# 2V5_DRS4_SUPPLY.net
KiCad netlist of a schematic drawn in Altium Designer
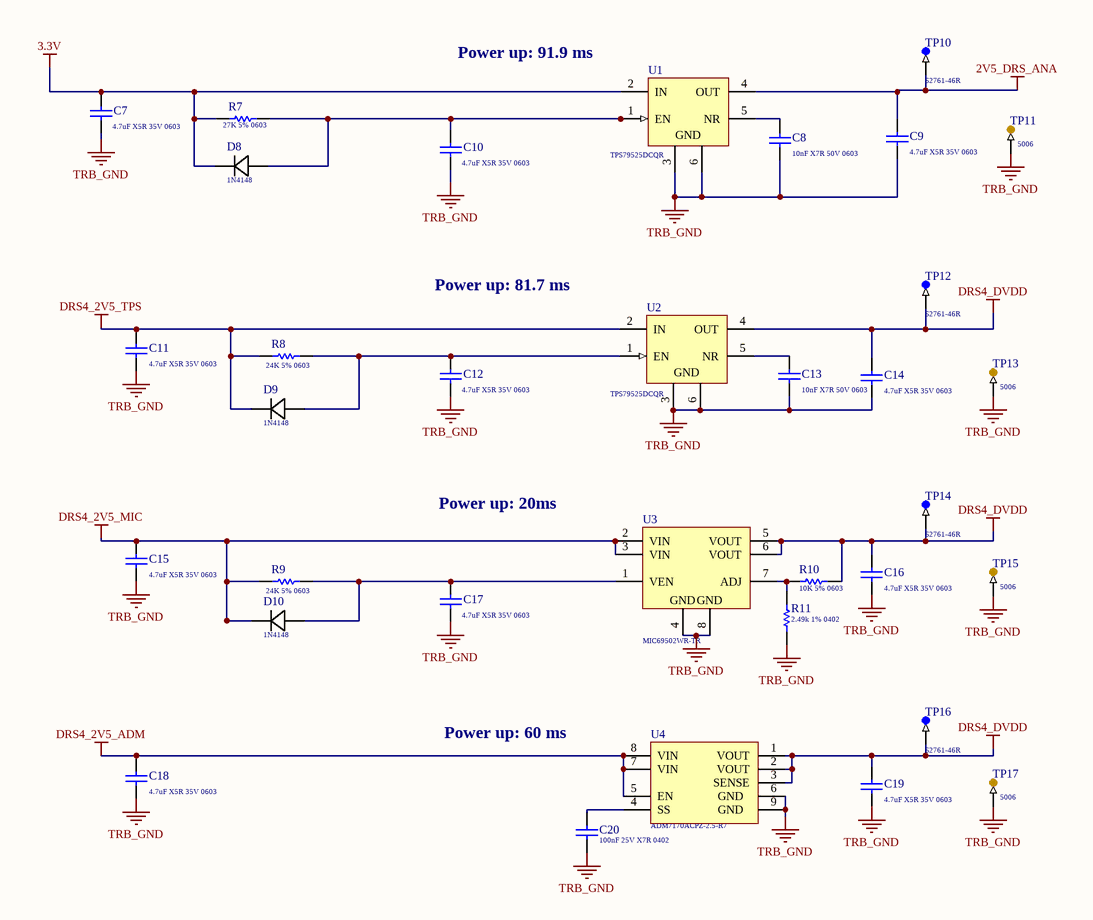
[diagram p0: 2V5_DRS4_SUPPLY.SchDoc]

(export (version "E")
  (design (tool "Eeschema 10.0.6"))
  (components
    (comp (ref "C7")
      (value "Cap_Murata_ZRB18AR6YA475ME05L_4.7uF")
      (footprint "Cap_Murata_ZRB18AR6YA475ME05L_4.7uF")
      (description "CAP CER 4.7uF 35V X5R 0603")
      (fields (field (name "CAPACITANCE") "4.7uF X5R 35V 0603"))
      (libsource (lib "Cap_Murata_ZRB18AR6YA475ME05L_4.7uF") (part "Cap_Murata_ZRB18AR6YA475ME05L_4.7uF"))
    )
    (comp (ref "C8")
      (value "Cap_Kemet_C0603C103J5RACTU_eec")
      (footprint "Kemet_C0603_0")
      (description "CAP CER 10nF 50V X7R 0603")
      (fields
        (field (name "PART NUMBER") "C0603C103J5RACTU")
        (field (name "MANUFACTURER") "Kemet")
        (field (name "CAPACITANCE") "10nF X7R 50V 0603")
      )
      (libsource (lib "Cap_Kemet_C0603C103J5RACTU_10nF") (part "Cap_Kemet_C0603C103J5RACTU_eec"))
    )
    (comp (ref "C9")
      (value "Cap_Murata_ZRB18AR6YA475ME05L_4.7uF")
      (footprint "Cap_Murata_ZRB18AR6YA475ME05L_4.7uF")
      (description "CAP CER 4.7uF 35V X5R 0603")
      (fields (field (name "CAPACITANCE") "4.7uF X5R 35V 0603"))
      (libsource (lib "Cap_Murata_ZRB18AR6YA475ME05L_4.7uF") (part "Cap_Murata_ZRB18AR6YA475ME05L_4.7uF"))
    )
    (comp (ref "C10")
      (value "Cap_Murata_ZRB18AR6YA475ME05L_4.7uF")
      (footprint "Cap_Murata_ZRB18AR6YA475ME05L_4.7uF")
      (description "CAP CER 4.7uF 35V X5R 0603")
      (fields (field (name "CAPACITANCE") "4.7uF X5R 35V 0603"))
      (libsource (lib "Cap_Murata_ZRB18AR6YA475ME05L_4.7uF") (part "Cap_Murata_ZRB18AR6YA475ME05L_4.7uF"))
    )
    (comp (ref "C11")
      (value "Cap_Murata_ZRB18AR6YA475ME05L_4.7uF")
      (footprint "Cap_Murata_ZRB18AR6YA475ME05L_4.7uF")
      (description "CAP CER 4.7uF 35V X5R 0603")
      (fields (field (name "CAPACITANCE") "4.7uF X5R 35V 0603"))
      (libsource (lib "Cap_Murata_ZRB18AR6YA475ME05L_4.7uF") (part "Cap_Murata_ZRB18AR6YA475ME05L_4.7uF"))
    )
    (comp (ref "C12")
      (value "Cap_Murata_ZRB18AR6YA475ME05L_4.7uF")
      (footprint "Cap_Murata_ZRB18AR6YA475ME05L_4.7uF")
      (description "CAP CER 4.7uF 35V X5R 0603")
      (fields (field (name "CAPACITANCE") "4.7uF X5R 35V 0603"))
      (libsource (lib "Cap_Murata_ZRB18AR6YA475ME05L_4.7uF") (part "Cap_Murata_ZRB18AR6YA475ME05L_4.7uF"))
    )
    (comp (ref "C13")
      (value "Cap_Kemet_C0603C103J5RACTU_eec")
      (footprint "Kemet_C0603_0")
      (description "CAP CER 10nF 50V X7R 0603")
      (fields
        (field (name "PART NUMBER") "C0603C103J5RACTU")
        (field (name "MANUFACTURER") "Kemet")
        (field (name "CAPACITANCE") "10nF X7R 50V 0603")
      )
      (libsource (lib "Cap_Kemet_C0603C103J5RACTU_10nF") (part "Cap_Kemet_C0603C103J5RACTU_eec"))
    )
    (comp (ref "C14")
      (value "Cap_Murata_ZRB18AR6YA475ME05L_4.7uF")
      (footprint "Cap_Murata_ZRB18AR6YA475ME05L_4.7uF")
      (description "CAP CER 4.7uF 35V X5R 0603")
      (fields (field (name "CAPACITANCE") "4.7uF X5R 35V 0603"))
      (libsource (lib "Cap_Murata_ZRB18AR6YA475ME05L_4.7uF") (part "Cap_Murata_ZRB18AR6YA475ME05L_4.7uF"))
    )
    (comp (ref "C15")
      (value "Cap_Murata_ZRB18AR6YA475ME05L_4.7uF")
      (footprint "Cap_Murata_ZRB18AR6YA475ME05L_4.7uF")
      (description "CAP CER 4.7uF 35V X5R 0603")
      (fields (field (name "CAPACITANCE") "4.7uF X5R 35V 0603"))
      (libsource (lib "Cap_Murata_ZRB18AR6YA475ME05L_4.7uF") (part "Cap_Murata_ZRB18AR6YA475ME05L_4.7uF"))
    )
    (comp (ref "C16")
      (value "Cap_Murata_ZRB18AR6YA475ME05L_4.7uF")
      (footprint "Cap_Murata_ZRB18AR6YA475ME05L_4.7uF")
      (description "CAP CER 4.7uF 35V X5R 0603")
      (fields (field (name "CAPACITANCE") "4.7uF X5R 35V 0603"))
      (libsource (lib "Cap_Murata_ZRB18AR6YA475ME05L_4.7uF") (part "Cap_Murata_ZRB18AR6YA475ME05L_4.7uF"))
    )
    (comp (ref "C17")
      (value "Cap_Murata_ZRB18AR6YA475ME05L_4.7uF")
      (footprint "Cap_Murata_ZRB18AR6YA475ME05L_4.7uF")
      (description "CAP CER 4.7uF 35V X5R 0603")
      (fields (field (name "CAPACITANCE") "4.7uF X5R 35V 0603"))
      (libsource (lib "Cap_Murata_ZRB18AR6YA475ME05L_4.7uF") (part "Cap_Murata_ZRB18AR6YA475ME05L_4.7uF"))
    )
    (comp (ref "C18")
      (value "Cap_Murata_ZRB18AR6YA475ME05L_4.7uF")
      (footprint "Cap_Murata_ZRB18AR6YA475ME05L_4.7uF")
      (description "CAP CER 4.7uF 35V X5R 0603")
      (fields (field (name "CAPACITANCE") "4.7uF X5R 35V 0603"))
      (libsource (lib "Cap_Murata_ZRB18AR6YA475ME05L_4.7uF") (part "Cap_Murata_ZRB18AR6YA475ME05L_4.7uF"))
    )
    (comp (ref "C19")
      (value "Cap_Murata_ZRB18AR6YA475ME05L_4.7uF")
      (footprint "Cap_Murata_ZRB18AR6YA475ME05L_4.7uF")
      (description "CAP CER 4.7uF 35V X5R 0603")
      (fields (field (name "CAPACITANCE") "4.7uF X5R 35V 0603"))
      (libsource (lib "Cap_Murata_ZRB18AR6YA475ME05L_4.7uF") (part "Cap_Murata_ZRB18AR6YA475ME05L_4.7uF"))
    )
    (comp (ref "C20")
      (value "Cap_Taiyo_Yuden_TMK105B7104KV-FR_100nF")
      (footprint "Cap_Taiyo_Yuden_TMK105B7104KV-FR_100nF")
      (description "CAP CER 100nF 25V X7R 0402")
      (fields (field (name "CAPACITANCE") "100nF 25V X7R 0402"))
      (libsource (lib "Cap_Taiyo_Yuden_TMK105B7104KV-FR_100nF") (part "Cap_Taiyo_Yuden_TMK105B7104KV-FR_100nF"))
    )
    (comp (ref "D8")
      (value "Diode_ON_Semiconductor_1N4148WT_300mA")
      (footprint "Diode_ON_Semiconductor_1N4148WT_300mA")
      (description "Diodes - General Purpose, Power, Switching SINGLE JUNC. 75V 4.0NS COMP")
      (fields (field (name "SERIES") "1N4148"))
      (libsource (lib "Diode_ON_Semiconductor_1N4148WT_300mA") (part "Diode_ON_Semiconductor_1N4148WT_300mA"))
    )
    (comp (ref "D9")
      (value "Diode_ON_Semiconductor_1N4148WT_300mA")
      (footprint "Diode_ON_Semiconductor_1N4148WT_300mA")
      (description "Diodes - General Purpose, Power, Switching SINGLE JUNC. 75V 4.0NS COMP")
      (fields (field (name "SERIES") "1N4148"))
      (libsource (lib "Diode_ON_Semiconductor_1N4148WT_300mA") (part "Diode_ON_Semiconductor_1N4148WT_300mA"))
    )
    (comp (ref "D10")
      (value "Diode_ON_Semiconductor_1N4148WT_300mA")
      (footprint "Diode_ON_Semiconductor_1N4148WT_300mA")
      (description "Diodes - General Purpose, Power, Switching SINGLE JUNC. 75V 4.0NS COMP")
      (fields (field (name "SERIES") "1N4148"))
      (libsource (lib "Diode_ON_Semiconductor_1N4148WT_300mA") (part "Diode_ON_Semiconductor_1N4148WT_300mA"))
    )
    (comp (ref "R7")
      (value "27K 5% 0603")
      (footprint "RESC0603(1608)_L")
      (description "27K 0.1W 5% 0603 (1608 Metric)  SMD")
      (fields (field (name "POWER") "0.1 W") (field (name "TOLERANCE") "5 %"))
      (libsource (lib "Altium Content Vault") (part "RES"))
    )
    (comp (ref "R8")
      (value "24K 5% 0603")
      (footprint "RESC0603(1608)_L")
      (description "24K 0.1W 5% 0603 (1608 Metric)  SMD")
      (fields (field (name "TOLERANCE") "5 %") (field (name "POWER") "0.1 W"))
      (libsource (lib "Altium Content Vault") (part "RES"))
    )
    (comp (ref "R9")
      (value "24K 5% 0603")
      (footprint "RESC0603(1608)_L")
      (description "24K 0.1W 5% 0603 (1608 Metric)  SMD")
      (fields (field (name "TOLERANCE") "5 %") (field (name "POWER") "0.1 W"))
      (libsource (lib "Altium Content Vault") (part "RES"))
    )
    (comp (ref "R10")
      (value "10K 5% 0603")
      (footprint "RESC0603(1608)_L")
      (description "10K 0.1W 5% 0603 (1608 Metric)  SMD")
      (fields (field (name "TOLERANCE") "5 %") (field (name "POWER") "0.1 W"))
      (libsource (lib "Altium Content Vault") (part "RES"))
    )
    (comp (ref "R11")
      (value "Res_Yageo_RC0402FR-132K49L_2.48kOhm")
      (footprint "Res_Yageo_RC0402FR-132K49L_2.48kOhm")
      (description "Thick Film Resistors - SMD 2.49K ohm 1% 50V General Purpose")
      (fields (field (name "RESISTANCE") "2.49k 1% 0402"))
      (libsource (lib "Res_Yageo_RC0402FR-132K49L_2.48kOhm") (part "Res_Yageo_RC0402FR-132K49L_2.48kOhm"))
    )
    (comp (ref "TP10")
      (value "TP_Harwin_S2761_46R")
      (footprint "TP_Harwin_S2761_46R")
      (description "Circuit Board Hardware - PCB SMT Mini Test Terminal, Reel")
      (fields (field (name "SERIES") "S2761-46R"))
      (libsource (lib "TP_Harwin_S2761_46R") (part "TP_Harwin_S2761_46R"))
    )
    (comp (ref "TP11")
      (value "TP_Keystone_Electronics_5006")
      (footprint "TP_Keystone_Electronics_5006")
      (description "Circuit Board Hardware - PCB TEST POINT BLK .063")
      (fields (field (name "SERIES") "5006"))
      (libsource (lib "TP_Keystone_Electronics_5006") (part "TP_Keystone_Electronics_5006"))
    )
    (comp (ref "TP12")
      (value "TP_Harwin_S2761_46R")
      (footprint "TP_Harwin_S2761_46R")
      (description "Circuit Board Hardware - PCB SMT Mini Test Terminal, Reel")
      (fields (field (name "SERIES") "S2761-46R"))
      (libsource (lib "TP_Harwin_S2761_46R") (part "TP_Harwin_S2761_46R"))
    )
    (comp (ref "TP13")
      (value "TP_Keystone_Electronics_5006")
      (footprint "TP_Keystone_Electronics_5006")
      (description "Circuit Board Hardware - PCB TEST POINT BLK .063")
      (fields (field (name "SERIES") "5006"))
      (libsource (lib "TP_Keystone_Electronics_5006") (part "TP_Keystone_Electronics_5006"))
    )
    (comp (ref "TP14")
      (value "TP_Harwin_S2761_46R")
      (footprint "TP_Harwin_S2761_46R")
      (description "Circuit Board Hardware - PCB SMT Mini Test Terminal, Reel")
      (fields (field (name "SERIES") "S2761-46R"))
      (libsource (lib "TP_Harwin_S2761_46R") (part "TP_Harwin_S2761_46R"))
    )
    (comp (ref "TP15")
      (value "TP_Keystone_Electronics_5006")
      (footprint "TP_Keystone_Electronics_5006")
      (description "Circuit Board Hardware - PCB TEST POINT BLK .063")
      (fields (field (name "SERIES") "5006"))
      (libsource (lib "TP_Keystone_Electronics_5006") (part "TP_Keystone_Electronics_5006"))
    )
    (comp (ref "TP16")
      (value "TP_Harwin_S2761_46R")
      (footprint "TP_Harwin_S2761_46R")
      (description "Circuit Board Hardware - PCB SMT Mini Test Terminal, Reel")
      (fields (field (name "SERIES") "S2761-46R"))
      (libsource (lib "TP_Harwin_S2761_46R") (part "TP_Harwin_S2761_46R"))
    )
    (comp (ref "TP17")
      (value "TP_Keystone_Electronics_5006")
      (footprint "TP_Keystone_Electronics_5006")
      (description "Circuit Board Hardware - PCB TEST POINT BLK .063")
      (fields (field (name "SERIES") "5006"))
      (libsource (lib "TP_Keystone_Electronics_5006") (part "TP_Keystone_Electronics_5006"))
    )
    (comp (ref "U1")
      (value "TPS79525DCQR")
      (footprint "DCQ0006A_N")
      (fields (field (name "MANUFACTURER") "Texas Instruments"))
      (libsource (lib "IC_Texas Instruments_TPS79525DCQR") (part "TPS79525DCQR"))
    )
    (comp (ref "U2")
      (value "TPS79525DCQR")
      (footprint "DCQ0006A_N")
      (fields (field (name "MANUFACTURER") "Texas Instruments"))
      (libsource (lib "IC_Texas Instruments_TPS79525DCQR") (part "TPS79525DCQR"))
    )
    (comp (ref "U3")
      (value "LDO_Microchip_MIC69502WR-TR_ADJ")
      (footprint "LDO_Microchip_MIC69502WR-TR_ADJ")
      (description "LDO Voltage Regulators 5A Low VIN LDO Regulator with 0.5Vref")
      (fields (field (name "SERIES") "MIC69502WR-TR"))
      (libsource (lib "LDO_Microchip_MIC69502WR-TR_ADJ") (part "LDO_Microchip_MIC69502WR-TR_ADJ"))
    )
    (comp (ref "U4")
      (value "LDO_Analog_Devices_ADM7170ACPZ-2.5-R7_2.5V")
      (footprint "LDO_Analog_Devices_ADM7170ACPZ-2.5-R7_2.5V")
      (description "LDO Voltage Regulators 0.5A Hi PSRR FT LDO 2.5V")
      (fields (field (name "SERIES") "ADM7170ACPZ-2.5-R7"))
      (libsource (lib "LDO_Analog_Devices_ADM7170ACPZ-2.5-R7_2.5V") (part "LDO_Analog_Devices_ADM7170ACPZ-2.5-R7_2.5V"))
    )
  )
  (nets
    (net (code "1") (name "2V5_DRS_ANA") (class "Default")
      (node (ref "C9") (pin "2") (pinfunction "2_2") (pintype "passive"))
      (node (ref "TP10") (pin "1") (pinfunction "1_1") (pintype "input"))
      (node (ref "U1") (pin "4") (pinfunction "OUT_4") (pintype "power_in"))
    )
    (net (code "2") (name "3.3V") (class "Default")
      (node (ref "C7") (pin "2") (pinfunction "2_2") (pintype "passive"))
      (node (ref "D8") (pin "1") (pinfunction "1_1") (pintype "passive"))
      (node (ref "R7") (pin "1") (pinfunction "1_1") (pintype "passive"))
      (node (ref "U1") (pin "2") (pinfunction "IN_2") (pintype "power_in"))
    )
    (net (code "3") (name "DRS4_2V5_ADM") (class "Default")
      (node (ref "C18") (pin "2") (pinfunction "2_2") (pintype "passive"))
      (node (ref "U4") (pin "5") (pinfunction "EN_5") (pintype "power_in"))
      (node (ref "U4") (pin "7") (pinfunction "VIN_7") (pintype "power_in"))
      (node (ref "U4") (pin "8") (pinfunction "VIN_8") (pintype "power_in"))
    )
    (net (code "4") (name "DRS4_2V5_MIC") (class "Default")
      (node (ref "C15") (pin "2") (pinfunction "2_2") (pintype "passive"))
      (node (ref "D10") (pin "1") (pinfunction "1_1") (pintype "passive"))
      (node (ref "R9") (pin "1") (pinfunction "1_1") (pintype "passive"))
      (node (ref "U3") (pin "2") (pinfunction "VIN_2") (pintype "power_in"))
      (node (ref "U3") (pin "3") (pinfunction "VIN_3") (pintype "power_in"))
    )
    (net (code "5") (name "DRS4_2V5_TPS") (class "Default")
      (node (ref "C11") (pin "2") (pinfunction "2_2") (pintype "passive"))
      (node (ref "D9") (pin "1") (pinfunction "1_1") (pintype "passive"))
      (node (ref "R8") (pin "1") (pinfunction "1_1") (pintype "passive"))
      (node (ref "U2") (pin "2") (pinfunction "IN_2") (pintype "power_in"))
    )
    (net (code "6") (name "DRS4_DVDD") (class "Default")
      (node (ref "C14") (pin "2") (pinfunction "2_2") (pintype "passive"))
      (node (ref "C16") (pin "2") (pinfunction "2_2") (pintype "passive"))
      (node (ref "C19") (pin "2") (pinfunction "2_2") (pintype "passive"))
      (node (ref "R10") (pin "2") (pinfunction "2_2") (pintype "passive"))
      (node (ref "TP12") (pin "1") (pinfunction "1_1") (pintype "input"))
      (node (ref "TP14") (pin "1") (pinfunction "1_1") (pintype "input"))
      (node (ref "TP16") (pin "1") (pinfunction "1_1") (pintype "input"))
      (node (ref "U2") (pin "4") (pinfunction "OUT_4") (pintype "power_in"))
      (node (ref "U3") (pin "5") (pinfunction "VOUT_5") (pintype "power_in"))
      (node (ref "U3") (pin "6") (pinfunction "VOUT_6") (pintype "power_in"))
      (node (ref "U4") (pin "1") (pinfunction "VOUT_1") (pintype "power_in"))
      (node (ref "U4") (pin "2") (pinfunction "VOUT_2") (pintype "power_in"))
      (node (ref "U4") (pin "3") (pinfunction "SENSE_3") (pintype "power_in"))
    )
    (net (code "7") (name "Net-(U1-EN)") (class "Default")
      (node (ref "C10") (pin "2") (pinfunction "2_2") (pintype "passive"))
      (node (ref "D8") (pin "2") (pinfunction "2_2") (pintype "passive"))
      (node (ref "R7") (pin "2") (pinfunction "2_2") (pintype "passive"))
      (node (ref "U1") (pin "1") (pinfunction "EN_1") (pintype "input"))
    )
    (net (code "8") (name "Net-(U1-NR)") (class "Default")
      (node (ref "C8") (pin "1") (pinfunction "1_1") (pintype "passive"))
      (node (ref "U1") (pin "5") (pinfunction "NR_5") (pintype "passive"))
    )
    (net (code "9") (name "Net-(U2-EN)") (class "Default")
      (node (ref "C12") (pin "2") (pinfunction "2_2") (pintype "passive"))
      (node (ref "D9") (pin "2") (pinfunction "2_2") (pintype "passive"))
      (node (ref "R8") (pin "2") (pinfunction "2_2") (pintype "passive"))
      (node (ref "U2") (pin "1") (pinfunction "EN_1") (pintype "input"))
    )
    (net (code "10") (name "Net-(U2-NR)") (class "Default")
      (node (ref "C13") (pin "1") (pinfunction "1_1") (pintype "passive"))
      (node (ref "U2") (pin "5") (pinfunction "NR_5") (pintype "passive"))
    )
    (net (code "11") (name "Net-(U3-ADJ)") (class "Default")
      (node (ref "R10") (pin "1") (pinfunction "1_1") (pintype "passive"))
      (node (ref "R11") (pin "2") (pinfunction "2_2") (pintype "passive"))
      (node (ref "U3") (pin "7") (pinfunction "ADJ_7") (pintype "power_in"))
    )
    (net (code "12") (name "Net-(U3-VEN)") (class "Default")
      (node (ref "C17") (pin "2") (pinfunction "2_2") (pintype "passive"))
      (node (ref "D10") (pin "2") (pinfunction "2_2") (pintype "passive"))
      (node (ref "R9") (pin "2") (pinfunction "2_2") (pintype "passive"))
      (node (ref "U3") (pin "1") (pinfunction "VEN_1") (pintype "power_in"))
    )
    (net (code "13") (name "Net-(U4-SS)") (class "Default")
      (node (ref "C20") (pin "2") (pinfunction "2_2") (pintype "passive"))
      (node (ref "U4") (pin "4") (pinfunction "SS_4") (pintype "power_in"))
    )
    (net (code "14") (name "TRB_GND") (class "Default")
      (node (ref "C10") (pin "1") (pinfunction "1_1") (pintype "passive"))
      (node (ref "C11") (pin "1") (pinfunction "1_1") (pintype "passive"))
      (node (ref "C12") (pin "1") (pinfunction "1_1") (pintype "passive"))
      (node (ref "C13") (pin "2") (pinfunction "2_2") (pintype "passive"))
      (node (ref "C14") (pin "1") (pinfunction "1_1") (pintype "passive"))
      (node (ref "C15") (pin "1") (pinfunction "1_1") (pintype "passive"))
      (node (ref "C16") (pin "1") (pinfunction "1_1") (pintype "passive"))
      (node (ref "C17") (pin "1") (pinfunction "1_1") (pintype "passive"))
      (node (ref "C18") (pin "1") (pinfunction "1_1") (pintype "passive"))
      (node (ref "C19") (pin "1") (pinfunction "1_1") (pintype "passive"))
      (node (ref "C20") (pin "1") (pinfunction "1_1") (pintype "passive"))
      (node (ref "C7") (pin "1") (pinfunction "1_1") (pintype "passive"))
      (node (ref "C8") (pin "2") (pinfunction "2_2") (pintype "passive"))
      (node (ref "C9") (pin "1") (pinfunction "1_1") (pintype "passive"))
      (node (ref "R11") (pin "1") (pinfunction "1_1") (pintype "passive"))
      (node (ref "TP11") (pin "1") (pinfunction "1_1") (pintype "input"))
      (node (ref "TP13") (pin "1") (pinfunction "1_1") (pintype "input"))
      (node (ref "TP15") (pin "1") (pinfunction "1_1") (pintype "input"))
      (node (ref "TP17") (pin "1") (pinfunction "1_1") (pintype "input"))
      (node (ref "U1") (pin "3") (pinfunction "GND_3") (pintype "power_in"))
      (node (ref "U1") (pin "6") (pinfunction "GND_6") (pintype "power_in"))
      (node (ref "U2") (pin "3") (pinfunction "GND_3") (pintype "power_in"))
      (node (ref "U2") (pin "6") (pinfunction "GND_6") (pintype "power_in"))
      (node (ref "U3") (pin "4") (pinfunction "GND_4") (pintype "power_in"))
      (node (ref "U3") (pin "8") (pinfunction "GND_8") (pintype "power_in"))
      (node (ref "U4") (pin "6") (pinfunction "GND_6") (pintype "power_in"))
      (node (ref "U4") (pin "9") (pinfunction "GND_9") (pintype "power_in"))
    )
  )
)
